# bldc_driver_board_easyeda_2.net
KiCad netlist of a schematic drawn in EasyEDA Pro
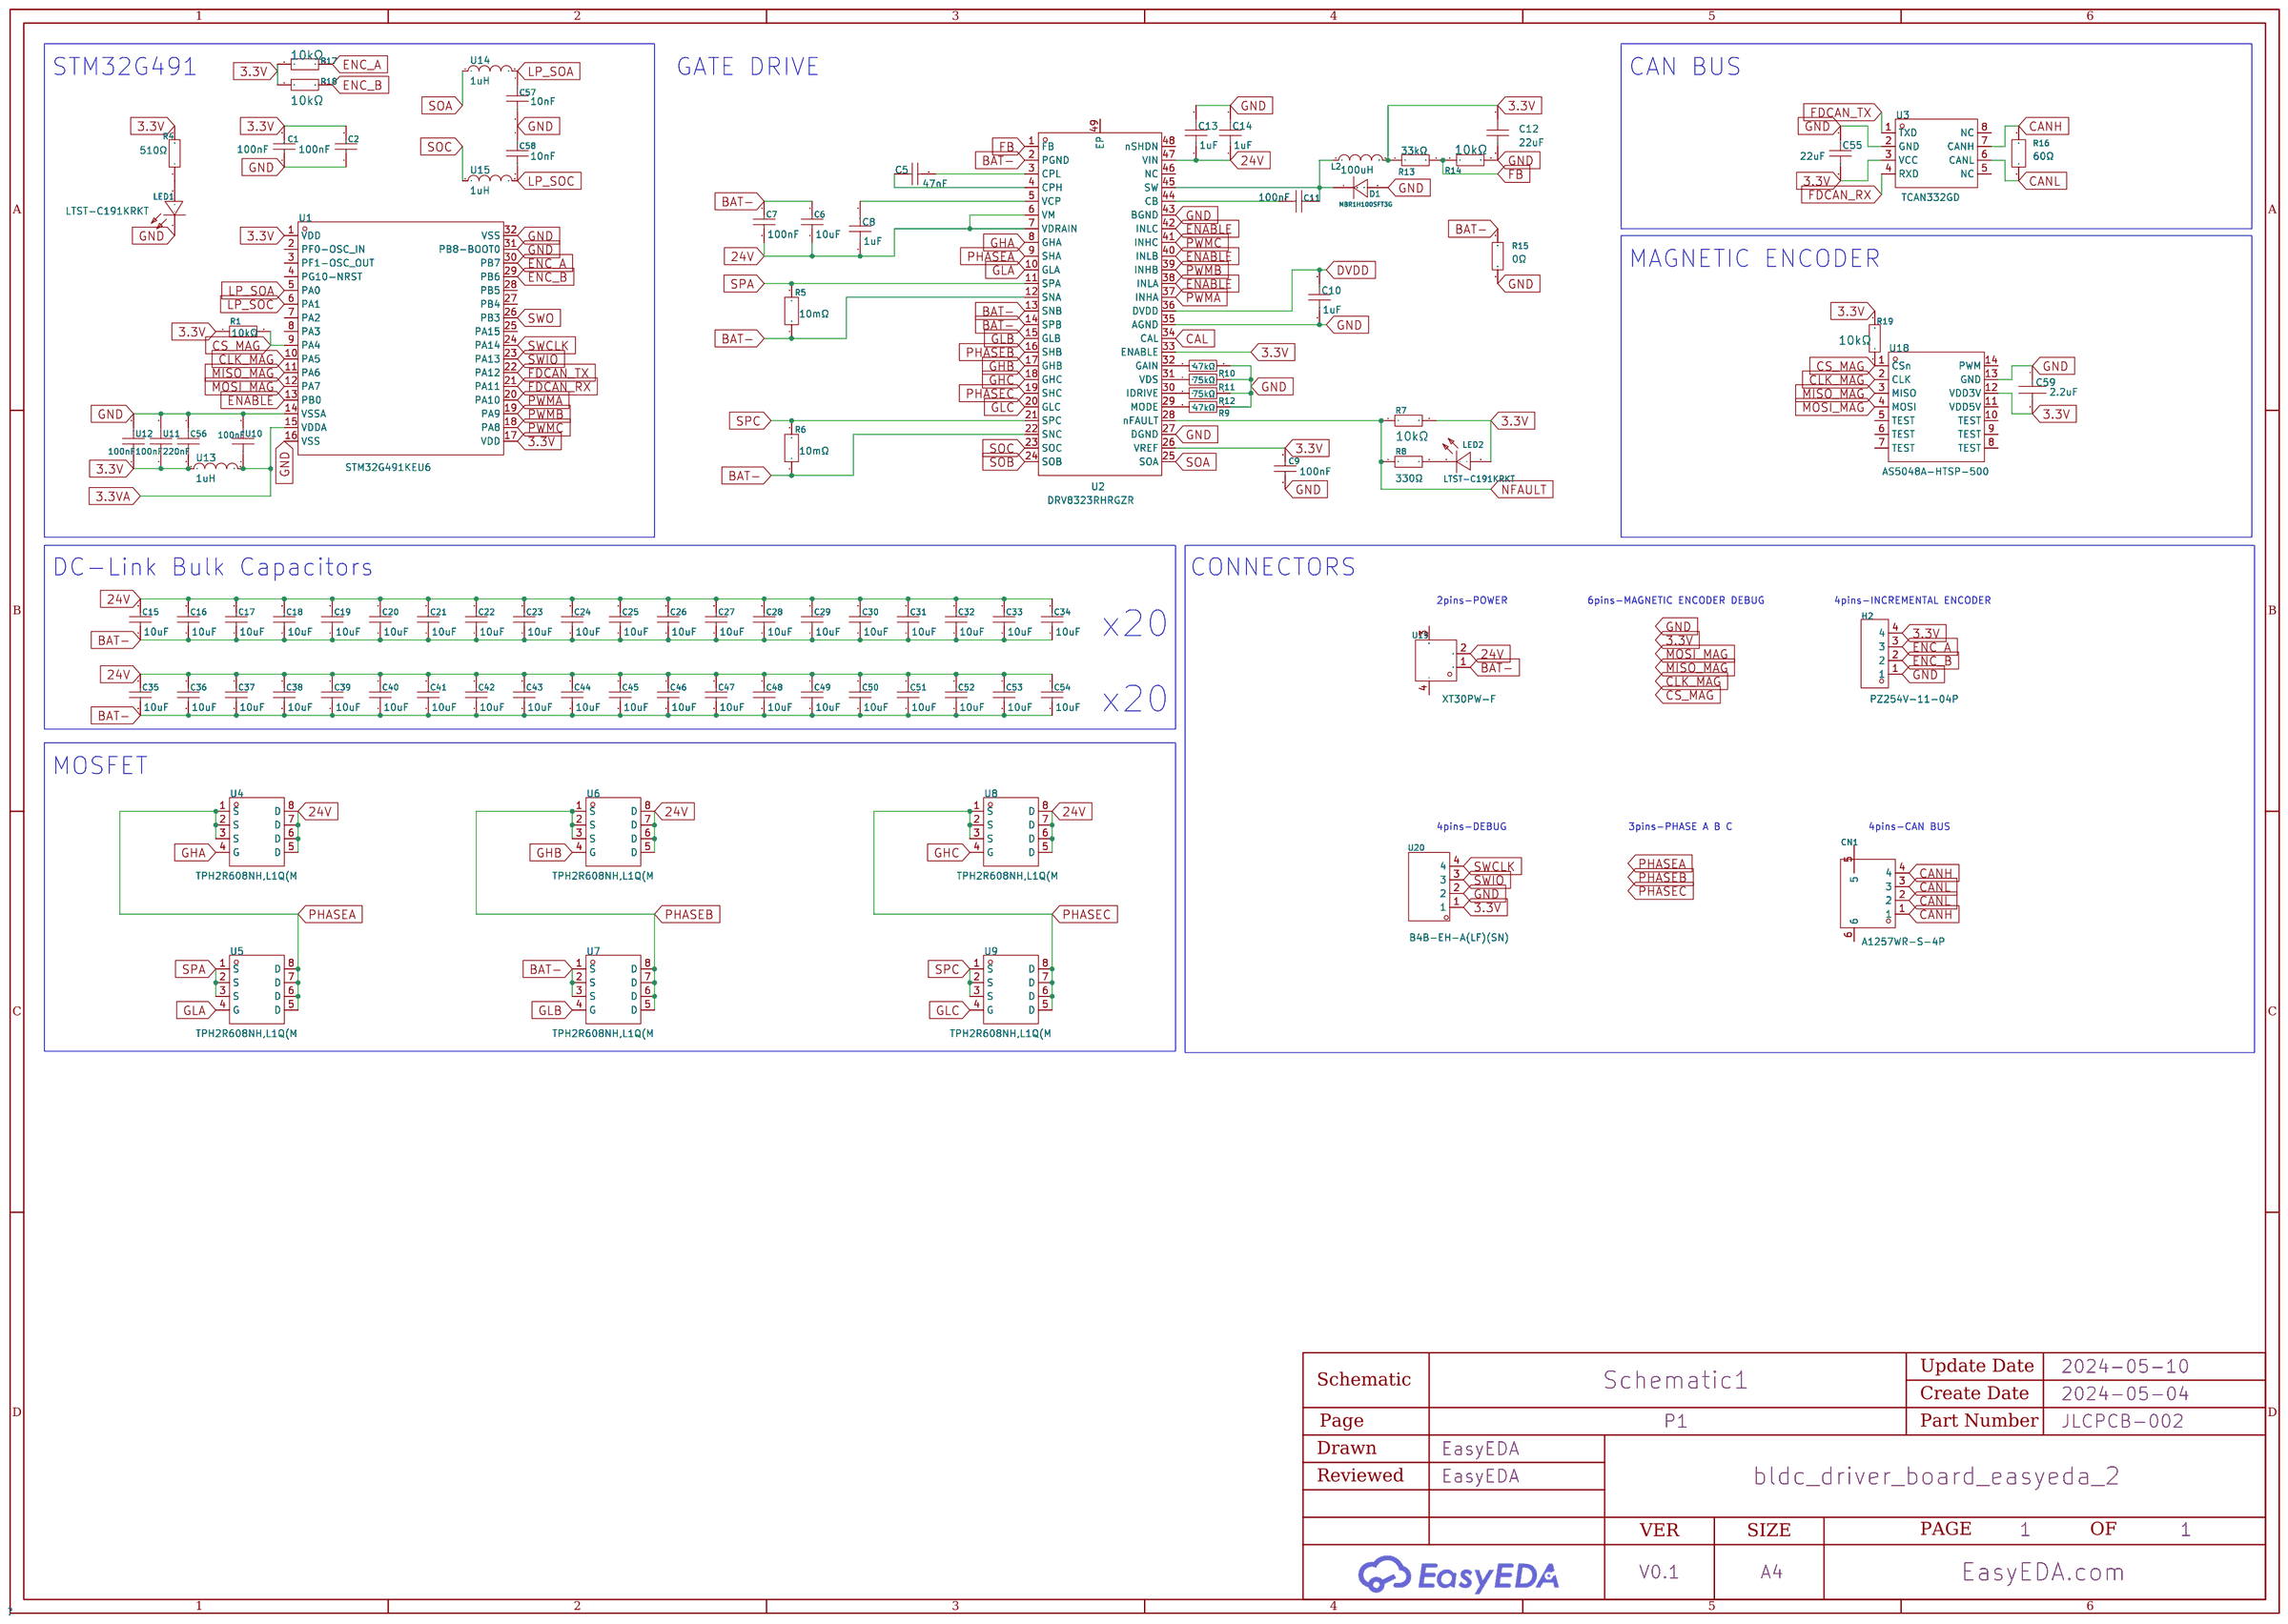
[diagram p0: schematic sheet]

(export (version "E")
  (design (tool "Eeschema 10.0.6"))
  (components
    (comp (ref "C1")
      (value "100nF")
      (footprint "easyedapro:C0603")
      (fields
        (field (name "Manufacturer Part") "CL10B104KO8NNNC")
        (field (name "Manufacturer") "SAMSUNG(三星)")
      )
      (libsource (lib "easyedapro") (part "CL10B104KO8NNNC"))
    )
    (comp (ref "C2")
      (value "100nF")
      (footprint "easyedapro:C0603")
      (fields
        (field (name "Manufacturer Part") "CL10B104KO8NNNC")
        (field (name "Manufacturer") "SAMSUNG(三星)")
      )
      (libsource (lib "easyedapro") (part "CL10B104KO8NNNC"))
    )
    (comp (ref "C5")
      (value "47nF")
      (footprint "easyedapro:C0805")
      (fields (field (name "Manufacturer Part") "0805B473K500NT") (field (name "Manufacturer") "FH(风华)"))
      (libsource (lib "easyedapro") (part "0805B473K500NT"))
    )
    (comp (ref "C6")
      (value "10uF")
      (footprint "easyedapro:C1206")
      (fields
        (field (name "Manufacturer Part") "CL31A106KBHNNNE")
        (field (name "Manufacturer") "SAMSUNG(三星)")
      )
      (libsource (lib "easyedapro") (part "CL31A106KBHNNNE"))
    )
    (comp (ref "C7")
      (value "100nF")
      (footprint "easyedapro:C1206")
      (fields (field (name "Manufacturer Part") "1206B104K500NT") (field (name "Manufacturer") "FH(风华)"))
      (libsource (lib "easyedapro") (part "1206B104K500NT"))
    )
    (comp (ref "C8")
      (value "1uF")
      (footprint "easyedapro:C0603")
      (fields
        (field (name "Manufacturer Part") "CL10A105KB8NNNC")
        (field (name "Manufacturer") "SAMSUNG(三星)")
      )
      (libsource (lib "easyedapro") (part "CL10A105KB8NNNC"))
    )
    (comp (ref "C9")
      (value "100nF")
      (footprint "easyedapro:C0603")
      (fields
        (field (name "Manufacturer Part") "CL10B104KO8NNNC")
        (field (name "Manufacturer") "SAMSUNG(三星)")
      )
      (libsource (lib "easyedapro") (part "CL10B104KO8NNNC"))
    )
    (comp (ref "C10")
      (value "1uF")
      (footprint "easyedapro:C0603")
      (fields
        (field (name "Manufacturer Part") "CL10A105KB8NNNC")
        (field (name "Manufacturer") "SAMSUNG(三星)")
      )
      (libsource (lib "easyedapro") (part "CL10A105KB8NNNC"))
    )
    (comp (ref "C11")
      (value "100nF")
      (footprint "easyedapro:C1206")
      (fields (field (name "Manufacturer Part") "1206B104K500NT") (field (name "Manufacturer") "FH(风华)"))
      (libsource (lib "easyedapro") (part "1206B104K500NT"))
    )
    (comp (ref "C12")
      (value "22uF")
      (footprint "easyedapro:C0603")
      (fields
        (field (name "Manufacturer Part") "CL10A226MQ8NRNE")
        (field (name "Manufacturer") "SAMSUNG(三星)")
      )
      (libsource (lib "easyedapro") (part "CL10A226MQ8NRNE"))
    )
    (comp (ref "C13")
      (value "1uF")
      (footprint "easyedapro:C0603")
      (fields
        (field (name "Manufacturer Part") "CL10A105KB8NNNC")
        (field (name "Manufacturer") "SAMSUNG(三星)")
      )
      (libsource (lib "easyedapro") (part "CL10A105KB8NNNC"))
    )
    (comp (ref "C14")
      (value "1uF")
      (footprint "easyedapro:C0603")
      (fields
        (field (name "Manufacturer Part") "CL10A105KB8NNNC")
        (field (name "Manufacturer") "SAMSUNG(三星)")
      )
      (libsource (lib "easyedapro") (part "CL10A105KB8NNNC"))
    )
    (comp (ref "C15")
      (value "10uF")
      (footprint "easyedapro:C1206")
      (fields
        (field (name "Manufacturer Part") "CL31A106KBHNNNE")
        (field (name "Manufacturer") "SAMSUNG(三星)")
      )
      (libsource (lib "easyedapro") (part "CL31A106KBHNNNE"))
    )
    (comp (ref "C16")
      (value "10uF")
      (footprint "easyedapro:C1206")
      (fields
        (field (name "Manufacturer Part") "CL31A106KBHNNNE")
        (field (name "Manufacturer") "SAMSUNG(三星)")
      )
      (libsource (lib "easyedapro") (part "CL31A106KBHNNNE"))
    )
    (comp (ref "C17")
      (value "10uF")
      (footprint "easyedapro:C1206")
      (fields
        (field (name "Manufacturer Part") "CL31A106KBHNNNE")
        (field (name "Manufacturer") "SAMSUNG(三星)")
      )
      (libsource (lib "easyedapro") (part "CL31A106KBHNNNE"))
    )
    (comp (ref "C18")
      (value "10uF")
      (footprint "easyedapro:C1206")
      (fields
        (field (name "Manufacturer Part") "CL31A106KBHNNNE")
        (field (name "Manufacturer") "SAMSUNG(三星)")
      )
      (libsource (lib "easyedapro") (part "CL31A106KBHNNNE"))
    )
    (comp (ref "C19")
      (value "10uF")
      (footprint "easyedapro:C1206")
      (fields
        (field (name "Manufacturer Part") "CL31A106KBHNNNE")
        (field (name "Manufacturer") "SAMSUNG(三星)")
      )
      (libsource (lib "easyedapro") (part "CL31A106KBHNNNE"))
    )
    (comp (ref "C20")
      (value "10uF")
      (footprint "easyedapro:C1206")
      (fields
        (field (name "Manufacturer Part") "CL31A106KBHNNNE")
        (field (name "Manufacturer") "SAMSUNG(三星)")
      )
      (libsource (lib "easyedapro") (part "CL31A106KBHNNNE"))
    )
    (comp (ref "C21")
      (value "10uF")
      (footprint "easyedapro:C1206")
      (fields
        (field (name "Manufacturer Part") "CL31A106KBHNNNE")
        (field (name "Manufacturer") "SAMSUNG(三星)")
      )
      (libsource (lib "easyedapro") (part "CL31A106KBHNNNE"))
    )
    (comp (ref "C22")
      (value "10uF")
      (footprint "easyedapro:C1206")
      (fields
        (field (name "Manufacturer Part") "CL31A106KBHNNNE")
        (field (name "Manufacturer") "SAMSUNG(三星)")
      )
      (libsource (lib "easyedapro") (part "CL31A106KBHNNNE"))
    )
    (comp (ref "C23")
      (value "10uF")
      (footprint "easyedapro:C1206")
      (fields
        (field (name "Manufacturer Part") "CL31A106KBHNNNE")
        (field (name "Manufacturer") "SAMSUNG(三星)")
      )
      (libsource (lib "easyedapro") (part "CL31A106KBHNNNE"))
    )
    (comp (ref "C24")
      (value "10uF")
      (footprint "easyedapro:C1206")
      (fields
        (field (name "Manufacturer Part") "CL31A106KBHNNNE")
        (field (name "Manufacturer") "SAMSUNG(三星)")
      )
      (libsource (lib "easyedapro") (part "CL31A106KBHNNNE"))
    )
    (comp (ref "C25")
      (value "10uF")
      (footprint "easyedapro:C1206")
      (fields
        (field (name "Manufacturer Part") "CL31A106KBHNNNE")
        (field (name "Manufacturer") "SAMSUNG(三星)")
      )
      (libsource (lib "easyedapro") (part "CL31A106KBHNNNE"))
    )
    (comp (ref "C26")
      (value "10uF")
      (footprint "easyedapro:C1206")
      (fields
        (field (name "Manufacturer Part") "CL31A106KBHNNNE")
        (field (name "Manufacturer") "SAMSUNG(三星)")
      )
      (libsource (lib "easyedapro") (part "CL31A106KBHNNNE"))
    )
    (comp (ref "C27")
      (value "10uF")
      (footprint "easyedapro:C1206")
      (fields
        (field (name "Manufacturer Part") "CL31A106KBHNNNE")
        (field (name "Manufacturer") "SAMSUNG(三星)")
      )
      (libsource (lib "easyedapro") (part "CL31A106KBHNNNE"))
    )
    (comp (ref "C28")
      (value "10uF")
      (footprint "easyedapro:C1206")
      (fields
        (field (name "Manufacturer Part") "CL31A106KBHNNNE")
        (field (name "Manufacturer") "SAMSUNG(三星)")
      )
      (libsource (lib "easyedapro") (part "CL31A106KBHNNNE"))
    )
    (comp (ref "C29")
      (value "10uF")
      (footprint "easyedapro:C1206")
      (fields
        (field (name "Manufacturer Part") "CL31A106KBHNNNE")
        (field (name "Manufacturer") "SAMSUNG(三星)")
      )
      (libsource (lib "easyedapro") (part "CL31A106KBHNNNE"))
    )
    (comp (ref "C30")
      (value "10uF")
      (footprint "easyedapro:C1206")
      (fields
        (field (name "Manufacturer Part") "CL31A106KBHNNNE")
        (field (name "Manufacturer") "SAMSUNG(三星)")
      )
      (libsource (lib "easyedapro") (part "CL31A106KBHNNNE"))
    )
    (comp (ref "C31")
      (value "10uF")
      (footprint "easyedapro:C1206")
      (fields
        (field (name "Manufacturer Part") "CL31A106KBHNNNE")
        (field (name "Manufacturer") "SAMSUNG(三星)")
      )
      (libsource (lib "easyedapro") (part "CL31A106KBHNNNE"))
    )
    (comp (ref "C32")
      (value "10uF")
      (footprint "easyedapro:C1206")
      (fields
        (field (name "Manufacturer Part") "CL31A106KBHNNNE")
        (field (name "Manufacturer") "SAMSUNG(三星)")
      )
      (libsource (lib "easyedapro") (part "CL31A106KBHNNNE"))
    )
    (comp (ref "C33")
      (value "10uF")
      (footprint "easyedapro:C1206")
      (fields
        (field (name "Manufacturer Part") "CL31A106KBHNNNE")
        (field (name "Manufacturer") "SAMSUNG(三星)")
      )
      (libsource (lib "easyedapro") (part "CL31A106KBHNNNE"))
    )
    (comp (ref "C34")
      (value "10uF")
      (footprint "easyedapro:C1206")
      (fields
        (field (name "Manufacturer Part") "CL31A106KBHNNNE")
        (field (name "Manufacturer") "SAMSUNG(三星)")
      )
      (libsource (lib "easyedapro") (part "CL31A106KBHNNNE"))
    )
    (comp (ref "C35")
      (value "10uF")
      (footprint "easyedapro:C1206")
      (fields
        (field (name "Manufacturer Part") "CL31A106KBHNNNE")
        (field (name "Manufacturer") "SAMSUNG(三星)")
      )
      (libsource (lib "easyedapro") (part "CL31A106KBHNNNE"))
    )
    (comp (ref "C36")
      (value "10uF")
      (footprint "easyedapro:C1206")
      (fields
        (field (name "Manufacturer Part") "CL31A106KBHNNNE")
        (field (name "Manufacturer") "SAMSUNG(三星)")
      )
      (libsource (lib "easyedapro") (part "CL31A106KBHNNNE"))
    )
    (comp (ref "C37")
      (value "10uF")
      (footprint "easyedapro:C1206")
      (fields
        (field (name "Manufacturer Part") "CL31A106KBHNNNE")
        (field (name "Manufacturer") "SAMSUNG(三星)")
      )
      (libsource (lib "easyedapro") (part "CL31A106KBHNNNE"))
    )
    (comp (ref "C38")
      (value "10uF")
      (footprint "easyedapro:C1206")
      (fields
        (field (name "Manufacturer Part") "CL31A106KBHNNNE")
        (field (name "Manufacturer") "SAMSUNG(三星)")
      )
      (libsource (lib "easyedapro") (part "CL31A106KBHNNNE"))
    )
    (comp (ref "C39")
      (value "10uF")
      (footprint "easyedapro:C1206")
      (fields
        (field (name "Manufacturer Part") "CL31A106KBHNNNE")
        (field (name "Manufacturer") "SAMSUNG(三星)")
      )
      (libsource (lib "easyedapro") (part "CL31A106KBHNNNE"))
    )
    (comp (ref "C40")
      (value "10uF")
      (footprint "easyedapro:C1206")
      (fields
        (field (name "Manufacturer Part") "CL31A106KBHNNNE")
        (field (name "Manufacturer") "SAMSUNG(三星)")
      )
      (libsource (lib "easyedapro") (part "CL31A106KBHNNNE"))
    )
    (comp (ref "C41")
      (value "10uF")
      (footprint "easyedapro:C1206")
      (fields
        (field (name "Manufacturer Part") "CL31A106KBHNNNE")
        (field (name "Manufacturer") "SAMSUNG(三星)")
      )
      (libsource (lib "easyedapro") (part "CL31A106KBHNNNE"))
    )
    (comp (ref "C42")
      (value "10uF")
      (footprint "easyedapro:C1206")
      (fields
        (field (name "Manufacturer Part") "CL31A106KBHNNNE")
        (field (name "Manufacturer") "SAMSUNG(三星)")
      )
      (libsource (lib "easyedapro") (part "CL31A106KBHNNNE"))
    )
    (comp (ref "C43")
      (value "10uF")
      (footprint "easyedapro:C1206")
      (fields
        (field (name "Manufacturer Part") "CL31A106KBHNNNE")
        (field (name "Manufacturer") "SAMSUNG(三星)")
      )
      (libsource (lib "easyedapro") (part "CL31A106KBHNNNE"))
    )
    (comp (ref "C44")
      (value "10uF")
      (footprint "easyedapro:C1206")
      (fields
        (field (name "Manufacturer Part") "CL31A106KBHNNNE")
        (field (name "Manufacturer") "SAMSUNG(三星)")
      )
      (libsource (lib "easyedapro") (part "CL31A106KBHNNNE"))
    )
    (comp (ref "C45")
      (value "10uF")
      (footprint "easyedapro:C1206")
      (fields
        (field (name "Manufacturer Part") "CL31A106KBHNNNE")
        (field (name "Manufacturer") "SAMSUNG(三星)")
      )
      (libsource (lib "easyedapro") (part "CL31A106KBHNNNE"))
    )
    (comp (ref "C46")
      (value "10uF")
      (footprint "easyedapro:C1206")
      (fields
        (field (name "Manufacturer Part") "CL31A106KBHNNNE")
        (field (name "Manufacturer") "SAMSUNG(三星)")
      )
      (libsource (lib "easyedapro") (part "CL31A106KBHNNNE"))
    )
    (comp (ref "C47")
      (value "10uF")
      (footprint "easyedapro:C1206")
      (fields
        (field (name "Manufacturer Part") "CL31A106KBHNNNE")
        (field (name "Manufacturer") "SAMSUNG(三星)")
      )
      (libsource (lib "easyedapro") (part "CL31A106KBHNNNE"))
    )
    (comp (ref "C48")
      (value "10uF")
      (footprint "easyedapro:C1206")
      (fields
        (field (name "Manufacturer Part") "CL31A106KBHNNNE")
        (field (name "Manufacturer") "SAMSUNG(三星)")
      )
      (libsource (lib "easyedapro") (part "CL31A106KBHNNNE"))
    )
    (comp (ref "C49")
      (value "10uF")
      (footprint "easyedapro:C1206")
      (fields
        (field (name "Manufacturer Part") "CL31A106KBHNNNE")
        (field (name "Manufacturer") "SAMSUNG(三星)")
      )
      (libsource (lib "easyedapro") (part "CL31A106KBHNNNE"))
    )
    (comp (ref "C50")
      (value "10uF")
      (footprint "easyedapro:C1206")
      (fields
        (field (name "Manufacturer Part") "CL31A106KBHNNNE")
        (field (name "Manufacturer") "SAMSUNG(三星)")
      )
      (libsource (lib "easyedapro") (part "CL31A106KBHNNNE"))
    )
    (comp (ref "C51")
      (value "10uF")
      (footprint "easyedapro:C1206")
      (fields
        (field (name "Manufacturer Part") "CL31A106KBHNNNE")
        (field (name "Manufacturer") "SAMSUNG(三星)")
      )
      (libsource (lib "easyedapro") (part "CL31A106KBHNNNE"))
    )
    (comp (ref "C52")
      (value "10uF")
      (footprint "easyedapro:C1206")
      (fields
        (field (name "Manufacturer Part") "CL31A106KBHNNNE")
        (field (name "Manufacturer") "SAMSUNG(三星)")
      )
      (libsource (lib "easyedapro") (part "CL31A106KBHNNNE"))
    )
    (comp (ref "C53")
      (value "10uF")
      (footprint "easyedapro:C1206")
      (fields
        (field (name "Manufacturer Part") "CL31A106KBHNNNE")
        (field (name "Manufacturer") "SAMSUNG(三星)")
      )
      (libsource (lib "easyedapro") (part "CL31A106KBHNNNE"))
    )
    (comp (ref "C54")
      (value "10uF")
      (footprint "easyedapro:C1206")
      (fields
        (field (name "Manufacturer Part") "CL31A106KBHNNNE")
        (field (name "Manufacturer") "SAMSUNG(三星)")
      )
      (libsource (lib "easyedapro") (part "CL31A106KBHNNNE"))
    )
    (comp (ref "C55")
      (value "22uF")
      (footprint "easyedapro:C0603")
      (fields
        (field (name "Manufacturer Part") "CL10A226MQ8NRNE")
        (field (name "Manufacturer") "SAMSUNG(三星)")
      )
      (libsource (lib "easyedapro") (part "CL10A226MQ8NRNE"))
    )
    (comp (ref "C56")
      (value "220nF")
      (footprint "easyedapro:C0201")
      (fields (field (name "Manufacturer Part") "C0603X5R0J224KT00NN") (field (name "Manufacturer") "TDK"))
      (libsource (lib "easyedapro") (part "C0603X5R0J224KT00NN"))
    )
    (comp (ref "C57")
      (value "10nF")
      (footprint "easyedapro:C01005")
      (fields
        (field (name "Manufacturer Part") "CC0603KRX7R9BB103")
        (field (name "Manufacturer") "YAGEO(国巨)")
      )
      (libsource (lib "easyedapro") (part "CC0100KRX5R5BB103"))
    )
    (comp (ref "C58")
      (value "10nF")
      (footprint "easyedapro:C01005")
      (fields
        (field (name "Manufacturer Part") "CC0603KRX7R9BB103")
        (field (name "Manufacturer") "YAGEO(国巨)")
      )
      (libsource (lib "easyedapro") (part "CC0100KRX5R5BB103"))
    )
    (comp (ref "C59")
      (value "2.2uF")
      (footprint "easyedapro:C0402")
      (fields
        (field (name "Manufacturer Part") "CL05A225MQ5NSNC")
        (field (name "Manufacturer") "SAMSUNG(三星)")
      )
      (libsource (lib "easyedapro") (part "CL05A225MQ5NSNC"))
    )
    (comp (ref "CN1")
      (value "A1257WR-S-4P")
      (footprint "easyedapro:CONN-SMD_A1257WR-S-4P")
      (fields (field (name "Manufacturer") "CJT(长江连接器)"))
      (libsource (lib "easyedapro") (part "A1257WR-S-4P"))
    )
    (comp (ref "D1")
      (value "MBR1H100SFT3G")
      (footprint "easyedapro:SOD-123F_L2.8-W1.8-LS3.7-RD")
      (fields (field (name "Manufacturer") "onsemi(安森美)"))
      (libsource (lib "easyedapro") (part "MBR1H100SFT3G"))
    )
    (comp (ref "H2")
      (value "PZ254V-11-04P")
      (footprint "easyedapro:HDR-TH_4P-P2.54-V-M")
      (fields (field (name "Manufacturer") "XFCN(兴飞)"))
      (libsource (lib "easyedapro") (part "PZ254V-11-04P"))
    )
    (comp (ref "L2")
      (value "100uH")
      (footprint "easyedapro:IND-SMD_L4.0-W4.0")
      (fields
        (field (name "Manufacturer Part") "ASPIAIG-S4035-101M-T")
        (field (name "Manufacturer") "ABRACON")
      )
      (libsource (lib "easyedapro") (part "ASPIAIG-S4035-101M-T"))
    )
    (comp (ref "LED1")
      (value "LTST-C191KRKT")
      (footprint "easyedapro:LED0603-RD")
      (fields (field (name "Manufacturer") "LITEON(光宝)"))
      (libsource (lib "easyedapro") (part "LTST-C191KRKT"))
    )
    (comp (ref "LED2")
      (value "LTST-C191KRKT")
      (footprint "easyedapro:LED0603-RD")
      (fields (field (name "Manufacturer") "LITEON(光宝)"))
      (libsource (lib "easyedapro") (part "LTST-C191KRKT"))
    )
    (comp (ref "R1")
      (value "10kΩ")
      (footprint "easyedapro:R0603")
      (fields
        (field (name "Manufacturer Part") "0603WAF1002T5E")
        (field (name "Manufacturer") "UNI-ROYAL(厚声)")
      )
      (libsource (lib "easyedapro") (part "0603WAF1002T5E"))
    )
    (comp (ref "R4")
      (value "510Ω")
      (footprint "easyedapro:R0603")
      (fields
        (field (name "Manufacturer Part") "0603WAF5100T5E")
        (field (name "Manufacturer") "UNI-ROYAL(厚声)")
      )
      (libsource (lib "easyedapro") (part "0603WAF5100T5E"))
    )
    (comp (ref "R5")
      (value "10mΩ")
      (footprint "easyedapro:RES-SMD_L6.4-W3.2-R2512")
      (fields
        (field (name "Manufacturer Part") "HoJLR2512-3W-10mR-1%")
        (field (name "Manufacturer") "Milliohm(毫欧)")
      )
      (libsource (lib "easyedapro") (part "HOJLR2512-3W-10MR-1%"))
    )
    (comp (ref "R6")
      (value "10mΩ")
      (footprint "easyedapro:RES-SMD_L6.4-W3.2-R2512")
      (fields
        (field (name "Manufacturer Part") "HoJLR2512-3W-10mR-1%")
        (field (name "Manufacturer") "Milliohm(毫欧)")
      )
      (libsource (lib "easyedapro") (part "HOJLR2512-3W-10MR-1%"))
    )
    (comp (ref "R7")
      (value "10kΩ")
      (footprint "easyedapro:R0603")
      (fields
        (field (name "Manufacturer Part") "0603WAF1002T5E")
        (field (name "Manufacturer") "UNI-ROYAL(厚声)")
      )
      (libsource (lib "easyedapro") (part "0603WAF1002T5E"))
    )
    (comp (ref "R8")
      (value "330Ω")
      (footprint "easyedapro:R0603")
      (fields
        (field (name "Manufacturer Part") "0603WAF3300T5E")
        (field (name "Manufacturer") "UNI-ROYAL(厚声)")
      )
      (libsource (lib "easyedapro") (part "0603WAF3300T5E"))
    )
    (comp (ref "R9")
      (value "47kΩ")
      (footprint "easyedapro:R0603")
      (fields
        (field (name "Manufacturer Part") "0603WAF4702T5E")
        (field (name "Manufacturer") "UNI-ROYAL(厚声)")
      )
      (libsource (lib "easyedapro") (part "0603WAF4702T5E"))
    )
    (comp (ref "R10")
      (value "47kΩ")
      (footprint "easyedapro:R0603")
      (fields
        (field (name "Manufacturer Part") "0603WAF4702T5E")
        (field (name "Manufacturer") "UNI-ROYAL(厚声)")
      )
      (libsource (lib "easyedapro") (part "0603WAF4702T5E"))
    )
    (comp (ref "R11")
      (value "75kΩ")
      (footprint "easyedapro:R0603")
      (fields
        (field (name "Manufacturer Part") "0603WAF7502T5E")
        (field (name "Manufacturer") "UNI-ROYAL(厚声)")
      )
      (libsource (lib "easyedapro") (part "0603WAF7502T5E"))
    )
    (comp (ref "R12")
      (value "75kΩ")
      (footprint "easyedapro:R0603")
      (fields
        (field (name "Manufacturer Part") "0603WAF7502T5E")
        (field (name "Manufacturer") "UNI-ROYAL(厚声)")
      )
      (libsource (lib "easyedapro") (part "0603WAF7502T5E"))
    )
    (comp (ref "R13")
      (value "33kΩ")
      (footprint "easyedapro:R0603")
      (fields
        (field (name "Manufacturer Part") "0603WAF3302T5E")
        (field (name "Manufacturer") "UNI-ROYAL(厚声)")
      )
      (libsource (lib "easyedapro") (part "0603WAF3302T5E"))
    )
    (comp (ref "R14")
      (value "10kΩ")
      (footprint "easyedapro:R0603")
      (fields
        (field (name "Manufacturer Part") "0603WAF1002T5E")
        (field (name "Manufacturer") "UNI-ROYAL(厚声)")
      )
      (libsource (lib "easyedapro") (part "0603WAF1002T5E"))
    )
    (comp (ref "R15")
      (value "0Ω")
      (footprint "easyedapro:R1206")
      (fields
        (field (name "Manufacturer Part") "1206W4F0000T5E")
        (field (name "Manufacturer") "UNI-ROYAL(厚声)")
      )
      (libsource (lib "easyedapro") (part "1206W4F0000T5E"))
    )
    (comp (ref "R16")
      (value "60Ω")
      (footprint "easyedapro:R0603")
      (fields (field (name "Manufacturer Part") "RTT0360R0FTP") (field (name "Manufacturer") "RALEC(旺诠)"))
      (libsource (lib "easyedapro") (part "RTT0360R0FTP"))
    )
    (comp (ref "R17")
      (value "10kΩ")
      (footprint "easyedapro:R0603")
      (fields
        (field (name "Manufacturer Part") "0603WAF1002T5E")
        (field (name "Manufacturer") "UNI-ROYAL(厚声)")
      )
      (libsource (lib "easyedapro") (part "0603WAF1002T5E"))
    )
    (comp (ref "R18")
      (value "10kΩ")
      (footprint "easyedapro:R0603")
      (fields
        (field (name "Manufacturer Part") "0603WAF1002T5E")
        (field (name "Manufacturer") "UNI-ROYAL(厚声)")
      )
      (libsource (lib "easyedapro") (part "0603WAF1002T5E"))
    )
    (comp (ref "R19")
      (value "10kΩ")
      (footprint "easyedapro:R0603")
      (fields
        (field (name "Manufacturer Part") "0603WAF1002T5E")
        (field (name "Manufacturer") "UNI-ROYAL(厚声)")
      )
      (libsource (lib "easyedapro") (part "0603WAF1002T5E"))
    )
    (comp (ref "U1")
      (value "STM32G491KEU6")
      (footprint "easyedapro:UFQFPN-32_L5.0-W5.0-P0.50-TL-1")
      (fields (field (name "Manufacturer") "ST(意法半导体)"))
      (libsource (lib "easyedapro") (part "STM32G491KEU6"))
    )
    (comp (ref "U2")
      (value "DRV8323RHRGZR")
      (footprint "easyedapro:VQFN-48_L7.0-W7.0-P0.50-TL-EP5.1")
      (fields (field (name "Manufacturer") "TI(德州仪器)"))
      (libsource (lib "easyedapro") (part "DRV8323RHRGZR"))
    )
    (comp (ref "U3")
      (value "TCAN332GD")
      (footprint "easyedapro:SOIC-8_L4.9-W3.9-P1.27-LS6.0-BL")
      (fields (field (name "Manufacturer") "TI(德州仪器)"))
      (libsource (lib "easyedapro") (part "TCAN332GD"))
    )
    (comp (ref "U4")
      (value "TPH2R608NH,L1Q(M")
      (footprint "easyedapro:POWERVDFN-8_L5.0-W5.0-P1.27-LS6.0-BL")
      (fields (field (name "Manufacturer") "TOSHIBA(东芝)"))
      (libsource (lib "easyedapro") (part "TPH2R608NH,L1Q(M"))
    )
    (comp (ref "U5")
      (value "TPH2R608NH,L1Q(M")
      (footprint "easyedapro:POWERVDFN-8_L5.0-W5.0-P1.27-LS6.0-BL")
      (fields (field (name "Manufacturer") "TOSHIBA(东芝)"))
      (libsource (lib "easyedapro") (part "TPH2R608NH,L1Q(M"))
    )
    (comp (ref "U6")
      (value "TPH2R608NH,L1Q(M")
      (footprint "easyedapro:POWERVDFN-8_L5.0-W5.0-P1.27-LS6.0-BL")
      (fields (field (name "Manufacturer") "TOSHIBA(东芝)"))
      (libsource (lib "easyedapro") (part "TPH2R608NH,L1Q(M"))
    )
    (comp (ref "U7")
      (value "TPH2R608NH,L1Q(M")
      (footprint "easyedapro:POWERVDFN-8_L5.0-W5.0-P1.27-LS6.0-BL")
      (fields (field (name "Manufacturer") "TOSHIBA(东芝)"))
      (libsource (lib "easyedapro") (part "TPH2R608NH,L1Q(M"))
    )
    (comp (ref "U8")
      (value "TPH2R608NH,L1Q(M")
      (footprint "easyedapro:POWERVDFN-8_L5.0-W5.0-P1.27-LS6.0-BL")
      (fields (field (name "Manufacturer") "TOSHIBA(东芝)"))
      (libsource (lib "easyedapro") (part "TPH2R608NH,L1Q(M"))
    )
    (comp (ref "U9")
      (value "TPH2R608NH,L1Q(M")
      (footprint "easyedapro:POWERVDFN-8_L5.0-W5.0-P1.27-LS6.0-BL")
      (fields (field (name "Manufacturer") "TOSHIBA(东芝)"))
      (libsource (lib "easyedapro") (part "TPH2R608NH,L1Q(M"))
    )
    (comp (ref "U10")
      (value "100nF")
      (footprint "easyedapro:C0603")
      (fields (field (name "Manufacturer Part") "06036D104KAT2A") (field (name "Manufacturer") "Kyocera AVX"))
      (libsource (lib "easyedapro") (part "06036D104KAT2A"))
    )
    (comp (ref "U11")
      (value "100nF")
      (footprint "easyedapro:C0603")
      (fields (field (name "Manufacturer Part") "06036D104KAT2A") (field (name "Manufacturer") "Kyocera AVX"))
      (libsource (lib "easyedapro") (part "06036D104KAT2A"))
    )
    (comp (ref "U12")
      (value "100nF")
      (footprint "easyedapro:C0603")
      (fields (field (name "Manufacturer Part") "06036D104KAT2A") (field (name "Manufacturer") "Kyocera AVX"))
      (libsource (lib "easyedapro") (part "06036D104KAT2A"))
    )
    (comp (ref "U13")
      (value "1uH")
      (footprint "easyedapro:L0603")
      (fields (field (name "Manufacturer Part") "YL160808-1R0K") (field (name "Manufacturer") "YJYCOIN(益嘉源)"))
      (libsource (lib "easyedapro") (part "YL160808-1R0K"))
    )
    (comp (ref "U14")
      (value "1uH")
      (footprint "easyedapro:L0603")
      (fields (field (name "Manufacturer Part") "YL160808-1R0K") (field (name "Manufacturer") "YJYCOIN(益嘉源)"))
      (libsource (lib "easyedapro") (part "YL160808-1R0K"))
    )
    (comp (ref "U15")
      (value "1uH")
      (footprint "easyedapro:L0603")
      (fields (field (name "Manufacturer Part") "YL160808-1R0K") (field (name "Manufacturer") "YJYCOIN(益嘉源)"))
      (libsource (lib "easyedapro") (part "YL160808-1R0K"))
    )
    (comp (ref "U18")
      (value "AS5048A-HTSP-500")
      (footprint "easyedapro:TSSOP-14_L5.0-W4.4-P0.65-LS6.4-BL")
      (fields (field (name "Manufacturer") "ams(艾迈斯半导体)"))
      (libsource (lib "easyedapro") (part "AS5048A-HTSP-500"))
    )
    (comp (ref "U19")
      (value "XT30PW-F")
      (footprint "easyedapro:CONN-TH_XT30PW-F-1")
      (fields (field (name "Manufacturer") "AMASS(艾迈斯)"))
      (libsource (lib "easyedapro") (part "XT30PW-F"))
    )
    (comp (ref "U20")
      (value "B4B-EH-A(LF)(SN)")
      (footprint "easyedapro:CONN-TH_B4B-EH-A-LF-SN")
      (fields (field (name "Manufacturer") "JST"))
      (libsource (lib "easyedapro") (part "B4B-EH-A(LF)(SN)"))
    )
  )
  (nets
    (net (code "1") (name "3.3V") (class "Default")
      (node (ref "C1") (pin "2") (pinfunction "2_2") (pintype "input"))
      (node (ref "C12") (pin "1") (pinfunction "1_1") (pintype "unspecified"))
      (node (ref "C2") (pin "2") (pinfunction "2_2") (pintype "input"))
      (node (ref "C55") (pin "2") (pinfunction "2_2") (pintype "unspecified"))
      (node (ref "C56") (pin "2") (pinfunction "2_2") (pintype "input"))
      (node (ref "C59") (pin "2") (pinfunction "2_2") (pintype "unspecified"))
      (node (ref "C9") (pin "2") (pinfunction "2_2") (pintype "input"))
      (node (ref "H2") (pin "4") (pinfunction "4_4") (pintype "unspecified"))
      (node (ref "L2") (pin "2") (pinfunction "2_2") (pintype "input"))
      (node (ref "LED2") (pin "2") (pinfunction "+_2") (pintype "input"))
      (node (ref "R1") (pin "1") (pinfunction "1_1") (pintype "input"))
      (node (ref "R13") (pin "1") (pinfunction "1_1") (pintype "input"))
      (node (ref "R17") (pin "1") (pinfunction "1_1") (pintype "input"))
      (node (ref "R18") (pin "1") (pinfunction "1_1") (pintype "input"))
      (node (ref "R19") (pin "2") (pinfunction "2_2") (pintype "input"))
      (node (ref "R4") (pin "2") (pinfunction "2_2") (pintype "input"))
      (node (ref "R7") (pin "2") (pinfunction "2_2") (pintype "input"))
      (node (ref "U1") (pin "1") (pinfunction "VDD_1") (pintype "unspecified"))
      (node (ref "U1") (pin "17") (pinfunction "VDD_17") (pintype "unspecified"))
      (node (ref "U11") (pin "1") (pinfunction "1_1") (pintype "unspecified"))
      (node (ref "U12") (pin "1") (pinfunction "1_1") (pintype "unspecified"))
      (node (ref "U13") (pin "1") (pinfunction "1_1") (pintype "unspecified"))
      (node (ref "U18") (pin "12") (pinfunction "VDD3V_12") (pintype "unspecified"))
      (node (ref "U2") (pin "26") (pinfunction "VREF_26") (pintype "input"))
      (node (ref "U2") (pin "33") (pinfunction "ENABLE_33") (pintype "input"))
      (node (ref "U20") (pin "1") (pinfunction "1_1") (pintype "input"))
      (node (ref "U3") (pin "3") (pinfunction "VCC_3") (pintype "unspecified"))
    )
    (net (code "2") (name "3.3VA") (class "Default")
      (node (ref "U1") (pin "15") (pinfunction "VDDA_15") (pintype "unspecified"))
      (node (ref "U10") (pin "1") (pinfunction "1_1") (pintype "unspecified"))
      (node (ref "U13") (pin "2") (pinfunction "2_2") (pintype "unspecified"))
    )
    (net (code "3") (name "24V") (class "Default")
      (node (ref "C13") (pin "1") (pinfunction "1_1") (pintype "unspecified"))
      (node (ref "C14") (pin "1") (pinfunction "1_1") (pintype "unspecified"))
      (node (ref "C15") (pin "2") (pinfunction "2_2") (pintype "input"))
      (node (ref "C16") (pin "2") (pinfunction "2_2") (pintype "input"))
      (node (ref "C17") (pin "2") (pinfunction "2_2") (pintype "input"))
      (node (ref "C18") (pin "2") (pinfunction "2_2") (pintype "input"))
      (node (ref "C19") (pin "2") (pinfunction "2_2") (pintype "input"))
      (node (ref "C20") (pin "2") (pinfunction "2_2") (pintype "input"))
      (node (ref "C21") (pin "2") (pinfunction "2_2") (pintype "input"))
      (node (ref "C22") (pin "2") (pinfunction "2_2") (pintype "input"))
      (node (ref "C23") (pin "2") (pinfunction "2_2") (pintype "input"))
      (node (ref "C24") (pin "2") (pinfunction "2_2") (pintype "input"))
      (node (ref "C25") (pin "2") (pinfunction "2_2") (pintype "input"))
      (node (ref "C26") (pin "2") (pinfunction "2_2") (pintype "input"))
      (node (ref "C27") (pin "2") (pinfunction "2_2") (pintype "input"))
      (node (ref "C28") (pin "2") (pinfunction "2_2") (pintype "input"))
      (node (ref "C29") (pin "2") (pinfunction "2_2") (pintype "input"))
      (node (ref "C30") (pin "2") (pinfunction "2_2") (pintype "input"))
      (node (ref "C31") (pin "2") (pinfunction "2_2") (pintype "input"))
      (node (ref "C32") (pin "2") (pinfunction "2_2") (pintype "input"))
      (node (ref "C33") (pin "2") (pinfunction "2_2") (pintype "input"))
      (node (ref "C34") (pin "2") (pinfunction "2_2") (pintype "input"))
      (node (ref "C35") (pin "2") (pinfunction "2_2") (pintype "input"))
      (node (ref "C36") (pin "2") (pinfunction "2_2") (pintype "input"))
      (node (ref "C37") (pin "2") (pinfunction "2_2") (pintype "input"))
      (node (ref "C38") (pin "2") (pinfunction "2_2") (pintype "input"))
      (node (ref "C39") (pin "2") (pinfunction "2_2") (pintype "input"))
      (node (ref "C40") (pin "2") (pinfunction "2_2") (pintype "input"))
      (node (ref "C41") (pin "2") (pinfunction "2_2") (pintype "input"))
      (node (ref "C42") (pin "2") (pinfunction "2_2") (pintype "input"))
      (node (ref "C43") (pin "2") (pinfunction "2_2") (pintype "input"))
      (node (ref "C44") (pin "2") (pinfunction "2_2") (pintype "input"))
      (node (ref "C45") (pin "2") (pinfunction "2_2") (pintype "input"))
      (node (ref "C46") (pin "2") (pinfunction "2_2") (pintype "input"))
      (node (ref "C47") (pin "2") (pinfunction "2_2") (pintype "input"))
      (node (ref "C48") (pin "2") (pinfunction "2_2") (pintype "input"))
      (node (ref "C49") (pin "2") (pinfunction "2_2") (pintype "input"))
      (node (ref "C50") (pin "2") (pinfunction "2_2") (pintype "input"))
      (node (ref "C51") (pin "2") (pinfunction "2_2") (pintype "input"))
      (node (ref "C52") (pin "2") (pinfunction "2_2") (pintype "input"))
      (node (ref "C53") (pin "2") (pinfunction "2_2") (pintype "input"))
      (node (ref "C54") (pin "2") (pinfunction "2_2") (pintype "input"))
      (node (ref "C6") (pin "1") (pinfunction "1_1") (pintype "input"))
      (node (ref "C7") (pin "1") (pinfunction "1_1") (pintype "input"))
      (node (ref "C8") (pin "1") (pinfunction "1_1") (pintype "unspecified"))
      (node (ref "U19") (pin "2") (pinfunction "2_2") (pintype "unspecified"))
      (node (ref "U2") (pin "47") (pinfunction "VIN_47") (pintype "input"))
      (node (ref "U2") (pin "6") (pinfunction "VM_6") (pintype "input"))
      (node (ref "U2") (pin "7") (pinfunction "VDRAIN_7") (pintype "input"))
      (node (ref "U4") (pin "5") (pinfunction "D_5") (pintype "input"))
      (node (ref "U4") (pin "6") (pinfunction "D_6") (pintype "input"))
      (node (ref "U4") (pin "7") (pinfunction "D_7") (pintype "input"))
      (node (ref "U4") (pin "8") (pinfunction "D_8") (pintype "input"))
      (node (ref "U6") (pin "5") (pinfunction "D_5") (pintype "input"))
      (node (ref "U6") (pin "6") (pinfunction "D_6") (pintype "input"))
      (node (ref "U6") (pin "7") (pinfunction "D_7") (pintype "input"))
      (node (ref "U6") (pin "8") (pinfunction "D_8") (pintype "input"))
      (node (ref "U8") (pin "5") (pinfunction "D_5") (pintype "input"))
      (node (ref "U8") (pin "6") (pinfunction "D_6") (pintype "input"))
      (node (ref "U8") (pin "7") (pinfunction "D_7") (pintype "input"))
      (node (ref "U8") (pin "8") (pinfunction "D_8") (pintype "input"))
    )
    (net (code "4") (name "BAT-") (class "Default")
      (node (ref "C15") (pin "1") (pinfunction "1_1") (pintype "input"))
      (node (ref "C16") (pin "1") (pinfunction "1_1") (pintype "input"))
      (node (ref "C17") (pin "1") (pinfunction "1_1") (pintype "input"))
      (node (ref "C18") (pin "1") (pinfunction "1_1") (pintype "input"))
      (node (ref "C19") (pin "1") (pinfunction "1_1") (pintype "input"))
      (node (ref "C20") (pin "1") (pinfunction "1_1") (pintype "input"))
      (node (ref "C21") (pin "1") (pinfunction "1_1") (pintype "input"))
      (node (ref "C22") (pin "1") (pinfunction "1_1") (pintype "input"))
      (node (ref "C23") (pin "1") (pinfunction "1_1") (pintype "input"))
      (node (ref "C24") (pin "1") (pinfunction "1_1") (pintype "input"))
      (node (ref "C25") (pin "1") (pinfunction "1_1") (pintype "input"))
      (node (ref "C26") (pin "1") (pinfunction "1_1") (pintype "input"))
      (node (ref "C27") (pin "1") (pinfunction "1_1") (pintype "input"))
      (node (ref "C28") (pin "1") (pinfunction "1_1") (pintype "input"))
      (node (ref "C29") (pin "1") (pinfunction "1_1") (pintype "input"))
      (node (ref "C30") (pin "1") (pinfunction "1_1") (pintype "input"))
      (node (ref "C31") (pin "1") (pinfunction "1_1") (pintype "input"))
      (node (ref "C32") (pin "1") (pinfunction "1_1") (pintype "input"))
      (node (ref "C33") (pin "1") (pinfunction "1_1") (pintype "input"))
      (node (ref "C34") (pin "1") (pinfunction "1_1") (pintype "input"))
      (node (ref "C35") (pin "1") (pinfunction "1_1") (pintype "input"))
      (node (ref "C36") (pin "1") (pinfunction "1_1") (pintype "input"))
      (node (ref "C37") (pin "1") (pinfunction "1_1") (pintype "input"))
      (node (ref "C38") (pin "1") (pinfunction "1_1") (pintype "input"))
      (node (ref "C39") (pin "1") (pinfunction "1_1") (pintype "input"))
      (node (ref "C40") (pin "1") (pinfunction "1_1") (pintype "input"))
      (node (ref "C41") (pin "1") (pinfunction "1_1") (pintype "input"))
      (node (ref "C42") (pin "1") (pinfunction "1_1") (pintype "input"))
      (node (ref "C43") (pin "1") (pinfunction "1_1") (pintype "input"))
      (node (ref "C44") (pin "1") (pinfunction "1_1") (pintype "input"))
      (node (ref "C45") (pin "1") (pinfunction "1_1") (pintype "input"))
      (node (ref "C46") (pin "1") (pinfunction "1_1") (pintype "input"))
      (node (ref "C47") (pin "1") (pinfunction "1_1") (pintype "input"))
      (node (ref "C48") (pin "1") (pinfunction "1_1") (pintype "input"))
      (node (ref "C49") (pin "1") (pinfunction "1_1") (pintype "input"))
      (node (ref "C50") (pin "1") (pinfunction "1_1") (pintype "input"))
      (node (ref "C51") (pin "1") (pinfunction "1_1") (pintype "input"))
      (node (ref "C52") (pin "1") (pinfunction "1_1") (pintype "input"))
      (node (ref "C53") (pin "1") (pinfunction "1_1") (pintype "input"))
      (node (ref "C54") (pin "1") (pinfunction "1_1") (pintype "input"))
      (node (ref "C6") (pin "2") (pinfunction "2_2") (pintype "input"))
      (node (ref "C7") (pin "2") (pinfunction "2_2") (pintype "input"))
      (node (ref "R15") (pin "2") (pinfunction "2_2") (pintype "input"))
      (node (ref "R5") (pin "1") (pinfunction "1_1") (pintype "input"))
      (node (ref "R6") (pin "1") (pinfunction "1_1") (pintype "input"))
      (node (ref "U19") (pin "1") (pinfunction "1_1") (pintype "unspecified"))
      (node (ref "U2") (pin "12") (pinfunction "SNA_12") (pintype "input"))
      (node (ref "U2") (pin "13") (pinfunction "SNB_13") (pintype "input"))
      (node (ref "U2") (pin "14") (pinfunction "SPB_14") (pintype "input"))
      (node (ref "U2") (pin "2") (pinfunction "PGND_2") (pintype "input"))
      (node (ref "U2") (pin "22") (pinfunction "SNC_22") (pintype "input"))
      (node (ref "U7") (pin "1") (pinfunction "S_1") (pintype "input"))
      (node (ref "U7") (pin "2") (pinfunction "S_2") (pintype "input"))
      (node (ref "U7") (pin "3") (pinfunction "S_3") (pintype "input"))
    )
    (net (code "5") (name "CAL") (class "Default")
      (node (ref "U2") (pin "34") (pinfunction "CAL_34") (pintype "input"))
    )
    (net (code "6") (name "CANH") (class "Default")
      (node (ref "CN1") (pin "1") (pinfunction "1_1") (pintype "input"))
      (node (ref "CN1") (pin "4") (pinfunction "4_4") (pintype "input"))
      (node (ref "R16") (pin "2") (pinfunction "2_2") (pintype "input"))
      (node (ref "U3") (pin "7") (pinfunction "CANH_7") (pintype "unspecified"))
    )
    (net (code "7") (name "CANL") (class "Default")
      (node (ref "CN1") (pin "2") (pinfunction "2_2") (pintype "input"))
      (node (ref "CN1") (pin "3") (pinfunction "3_3") (pintype "input"))
      (node (ref "R16") (pin "1") (pinfunction "1_1") (pintype "input"))
      (node (ref "U3") (pin "6") (pinfunction "CANL_6") (pintype "unspecified"))
    )
    (net (code "8") (name "CLK_MAG") (class "Default")
      (node (ref "U1") (pin "10") (pinfunction "PA5_10") (pintype "unspecified"))
      (node (ref "U18") (pin "2") (pinfunction "CLK_2") (pintype "unspecified"))
    )
    (net (code "9") (name "CS_MAG") (class "Default")
      (node (ref "R1") (pin "2") (pinfunction "2_2") (pintype "input"))
      (node (ref "R19") (pin "1") (pinfunction "1_1") (pintype "input"))
      (node (ref "U1") (pin "9") (pinfunction "PA4_9") (pintype "unspecified"))
      (node (ref "U18") (pin "1") (pinfunction "CSn_1") (pintype "unspecified"))
    )
    (net (code "10") (name "DVDD") (class "Default")
      (node (ref "C10") (pin "2") (pinfunction "2_2") (pintype "unspecified"))
      (node (ref "U2") (pin "36") (pinfunction "DVDD_36") (pintype "input"))
    )
    (net (code "11") (name "ENABLE") (class "Default")
      (node (ref "U1") (pin "13") (pinfunction "PB0_13") (pintype "unspecified"))
      (node (ref "U2") (pin "38") (pinfunction "INLA_38") (pintype "input"))
      (node (ref "U2") (pin "40") (pinfunction "INLB_40") (pintype "input"))
      (node (ref "U2") (pin "42") (pinfunction "INLC_42") (pintype "input"))
    )
    (net (code "12") (name "ENC_A") (class "Default")
      (node (ref "H2") (pin "3") (pinfunction "3_3") (pintype "unspecified"))
      (node (ref "R17") (pin "2") (pinfunction "2_2") (pintype "input"))
      (node (ref "U1") (pin "30") (pinfunction "PB7_30") (pintype "unspecified"))
    )
    (net (code "13") (name "ENC_B") (class "Default")
      (node (ref "H2") (pin "2") (pinfunction "2_2") (pintype "unspecified"))
      (node (ref "R18") (pin "2") (pinfunction "2_2") (pintype "input"))
      (node (ref "U1") (pin "29") (pinfunction "PB6_29") (pintype "unspecified"))
    )
    (net (code "14") (name "FB") (class "Default")
      (node (ref "R13") (pin "2") (pinfunction "2_2") (pintype "input"))
      (node (ref "R14") (pin "1") (pinfunction "1_1") (pintype "input"))
      (node (ref "U2") (pin "1") (pinfunction "FB_1") (pintype "input"))
    )
    (net (code "15") (name "FDCAN_RX") (class "Default")
      (node (ref "U1") (pin "21") (pinfunction "PA11_21") (pintype "unspecified"))
      (node (ref "U3") (pin "4") (pinfunction "RXD_4") (pintype "unspecified"))
    )
    (net (code "16") (name "FDCAN_TX") (class "Default")
      (node (ref "U1") (pin "22") (pinfunction "PA12_22") (pintype "unspecified"))
      (node (ref "U3") (pin "1") (pinfunction "TXD_1") (pintype "unspecified"))
    )
    (net (code "17") (name "GHA") (class "Default")
      (node (ref "U2") (pin "8") (pinfunction "GHA_8") (pintype "input"))
      (node (ref "U4") (pin "4") (pinfunction "G_4") (pintype "input"))
    )
    (net (code "18") (name "GHB") (class "Default")
      (node (ref "U2") (pin "17") (pinfunction "GHB_17") (pintype "input"))
      (node (ref "U6") (pin "4") (pinfunction "G_4") (pintype "input"))
    )
    (net (code "19") (name "GHC") (class "Default")
      (node (ref "U2") (pin "18") (pinfunction "GHC_18") (pintype "input"))
      (node (ref "U8") (pin "4") (pinfunction "G_4") (pintype "input"))
    )
    (net (code "20") (name "GLA") (class "Default")
      (node (ref "U2") (pin "10") (pinfunction "GLA_10") (pintype "input"))
      (node (ref "U5") (pin "4") (pinfunction "G_4") (pintype "input"))
    )
    (net (code "21") (name "GLB") (class "Default")
      (node (ref "U2") (pin "15") (pinfunction "GLB_15") (pintype "input"))
      (node (ref "U7") (pin "4") (pinfunction "G_4") (pintype "input"))
    )
    (net (code "22") (name "GLC") (class "Default")
      (node (ref "U2") (pin "20") (pinfunction "GLC_20") (pintype "input"))
      (node (ref "U9") (pin "4") (pinfunction "G_4") (pintype "input"))
    )
    (net (code "23") (name "GND") (class "Default")
      (node (ref "C1") (pin "1") (pinfunction "1_1") (pintype "input"))
      (node (ref "C10") (pin "1") (pinfunction "1_1") (pintype "unspecified"))
      (node (ref "C12") (pin "2") (pinfunction "2_2") (pintype "unspecified"))
      (node (ref "C13") (pin "2") (pinfunction "2_2") (pintype "unspecified"))
      (node (ref "C14") (pin "2") (pinfunction "2_2") (pintype "unspecified"))
      (node (ref "C2") (pin "1") (pinfunction "1_1") (pintype "input"))
      (node (ref "C55") (pin "1") (pinfunction "1_1") (pintype "unspecified"))
      (node (ref "C56") (pin "1") (pinfunction "1_1") (pintype "input"))
      (node (ref "C57") (pin "2") (pinfunction "2_2") (pintype "input"))
      (node (ref "C58") (pin "1") (pinfunction "1_1") (pintype "input"))
      (node (ref "C59") (pin "1") (pinfunction "1_1") (pintype "unspecified"))
      (node (ref "C9") (pin "1") (pinfunction "1_1") (pintype "input"))
      (node (ref "D1") (pin "2") (pinfunction "A_2") (pintype "input"))
      (node (ref "H2") (pin "1") (pinfunction "1_1") (pintype "unspecified"))
      (node (ref "LED1") (pin "1") (pinfunction "-_1") (pintype "input"))
      (node (ref "R10") (pin "2") (pinfunction "2_2") (pintype "input"))
      (node (ref "R11") (pin "2") (pinfunction "2_2") (pintype "input"))
      (node (ref "R12") (pin "2") (pinfunction "2_2") (pintype "input"))
      (node (ref "R14") (pin "2") (pinfunction "2_2") (pintype "input"))
      (node (ref "R15") (pin "1") (pinfunction "1_1") (pintype "input"))
      (node (ref "R9") (pin "2") (pinfunction "2_2") (pintype "input"))
      (node (ref "U1") (pin "14") (pinfunction "VSSA_14") (pintype "unspecified"))
      (node (ref "U1") (pin "16") (pinfunction "VSS_16") (pintype "unspecified"))
      (node (ref "U1") (pin "31") (pinfunction "PB8-BOOT0_31") (pintype "unspecified"))
      (node (ref "U1") (pin "32") (pinfunction "VSS_32") (pintype "unspecified"))
      (node (ref "U10") (pin "2") (pinfunction "2_2") (pintype "unspecified"))
      (node (ref "U11") (pin "2") (pinfunction "2_2") (pintype "unspecified"))
      (node (ref "U12") (pin "2") (pinfunction "2_2") (pintype "unspecified"))
      (node (ref "U18") (pin "13") (pinfunction "GND_13") (pintype "unspecified"))
      (node (ref "U2") (pin "27") (pinfunction "DGND_27") (pintype "input"))
      (node (ref "U2") (pin "35") (pinfunction "AGND_35") (pintype "input"))
      (node (ref "U2") (pin "43") (pinfunction "BGND_43") (pintype "input"))
      (node (ref "U20") (pin "2") (pinfunction "2_2") (pintype "input"))
      (node (ref "U3") (pin "2") (pinfunction "GND_2") (pintype "unspecified"))
    )
    (net (code "24") (name "LP_SOA") (class "Default")
      (node (ref "C57") (pin "1") (pinfunction "1_1") (pintype "input"))
      (node (ref "U1") (pin "5") (pinfunction "PA0_5") (pintype "unspecified"))
      (node (ref "U14") (pin "2") (pinfunction "2_2") (pintype "unspecified"))
    )
    (net (code "25") (name "LP_SOC") (class "Default")
      (node (ref "C58") (pin "2") (pinfunction "2_2") (pintype "input"))
      (node (ref "U1") (pin "6") (pinfunction "PA1_6") (pintype "unspecified"))
      (node (ref "U15") (pin "2") (pinfunction "2_2") (pintype "unspecified"))
    )
    (net (code "26") (name "MISO_MAG") (class "Default")
      (node (ref "U1") (pin "11") (pinfunction "PA6_11") (pintype "unspecified"))
      (node (ref "U18") (pin "3") (pinfunction "MISO_3") (pintype "unspecified"))
    )
    (net (code "27") (name "MOSI_MAG") (class "Default")
      (node (ref "U1") (pin "12") (pinfunction "PA7_12") (pintype "unspecified"))
      (node (ref "U18") (pin "4") (pinfunction "MOSI_4") (pintype "unspecified"))
    )
    (net (code "28") (name "NFAULT") (class "Default")
      (node (ref "R7") (pin "1") (pinfunction "1_1") (pintype "input"))
      (node (ref "R8") (pin "1") (pinfunction "1_1") (pintype "input"))
      (node (ref "U2") (pin "28") (pinfunction "nFAULT_28") (pintype "input"))
    )
    (net (code "29") (name "Net-(D1-C)") (class "Default")
      (node (ref "C11") (pin "1") (pinfunction "1_1") (pintype "input"))
      (node (ref "D1") (pin "1") (pinfunction "C_1") (pintype "input"))
      (node (ref "L2") (pin "1") (pinfunction "1_1") (pintype "input"))
      (node (ref "U2") (pin "45") (pinfunction "SW_45") (pintype "input"))
    )
    (net (code "30") (name "Net-(LED1-+)") (class "Default")
      (node (ref "LED1") (pin "2") (pinfunction "+_2") (pintype "input"))
      (node (ref "R4") (pin "1") (pinfunction "1_1") (pintype "input"))
    )
    (net (code "31") (name "Net-(LED2--)") (class "Default")
      (node (ref "LED2") (pin "1") (pinfunction "-_1") (pintype "input"))
      (node (ref "R8") (pin "2") (pinfunction "2_2") (pintype "input"))
    )
    (net (code "32") (name "Net-(U2-CB)") (class "Default")
      (node (ref "C11") (pin "2") (pinfunction "2_2") (pintype "input"))
      (node (ref "U2") (pin "44") (pinfunction "CB_44") (pintype "input"))
    )
    (net (code "33") (name "Net-(U2-CPH)") (class "Default")
      (node (ref "C5") (pin "1") (pinfunction "1_1") (pintype "input"))
      (node (ref "U2") (pin "4") (pinfunction "CPH_4") (pintype "input"))
    )
    (net (code "34") (name "Net-(U2-CPL)") (class "Default")
      (node (ref "C5") (pin "2") (pinfunction "2_2") (pintype "input"))
      (node (ref "U2") (pin "3") (pinfunction "CPL_3") (pintype "input"))
    )
    (net (code "35") (name "Net-(U2-GAIN)") (class "Default")
      (node (ref "R10") (pin "1") (pinfunction "1_1") (pintype "input"))
      (node (ref "U2") (pin "32") (pinfunction "GAIN_32") (pintype "input"))
    )
    (net (code "36") (name "Net-(U2-IDRIVE)") (class "Default")
      (node (ref "R12") (pin "1") (pinfunction "1_1") (pintype "input"))
      (node (ref "U2") (pin "30") (pinfunction "IDRIVE_30") (pintype "input"))
    )
    (net (code "37") (name "Net-(U2-MODE)") (class "Default")
      (node (ref "R9") (pin "1") (pinfunction "1_1") (pintype "input"))
      (node (ref "U2") (pin "29") (pinfunction "MODE_29") (pintype "input"))
    )
    (net (code "38") (name "Net-(U2-VCP)") (class "Default")
      (node (ref "C8") (pin "2") (pinfunction "2_2") (pintype "unspecified"))
      (node (ref "U2") (pin "5") (pinfunction "VCP_5") (pintype "input"))
    )
    (net (code "39") (name "Net-(U2-VDS)") (class "Default")
      (node (ref "R11") (pin "1") (pinfunction "1_1") (pintype "input"))
      (node (ref "U2") (pin "31") (pinfunction "VDS_31") (pintype "input"))
    )
    (net (code "40") (name "PHASEA") (class "Default")
      (node (ref "U2") (pin "9") (pinfunction "SHA_9") (pintype "input"))
      (node (ref "U4") (pin "1") (pinfunction "S_1") (pintype "input"))
      (node (ref "U4") (pin "2") (pinfunction "S_2") (pintype "input"))
      (node (ref "U4") (pin "3") (pinfunction "S_3") (pintype "input"))
      (node (ref "U5") (pin "5") (pinfunction "D_5") (pintype "input"))
      (node (ref "U5") (pin "6") (pinfunction "D_6") (pintype "input"))
      (node (ref "U5") (pin "7") (pinfunction "D_7") (pintype "input"))
      (node (ref "U5") (pin "8") (pinfunction "D_8") (pintype "input"))
    )
    (net (code "41") (name "PHASEB") (class "Default")
      (node (ref "U2") (pin "16") (pinfunction "SHB_16") (pintype "input"))
      (node (ref "U6") (pin "1") (pinfunction "S_1") (pintype "input"))
      (node (ref "U6") (pin "2") (pinfunction "S_2") (pintype "input"))
      (node (ref "U6") (pin "3") (pinfunction "S_3") (pintype "input"))
      (node (ref "U7") (pin "5") (pinfunction "D_5") (pintype "input"))
      (node (ref "U7") (pin "6") (pinfunction "D_6") (pintype "input"))
      (node (ref "U7") (pin "7") (pinfunction "D_7") (pintype "input"))
      (node (ref "U7") (pin "8") (pinfunction "D_8") (pintype "input"))
    )
    (net (code "42") (name "PHASEC") (class "Default")
      (node (ref "U2") (pin "19") (pinfunction "SHC_19") (pintype "input"))
      (node (ref "U8") (pin "1") (pinfunction "S_1") (pintype "input"))
      (node (ref "U8") (pin "2") (pinfunction "S_2") (pintype "input"))
      (node (ref "U8") (pin "3") (pinfunction "S_3") (pintype "input"))
      (node (ref "U9") (pin "5") (pinfunction "D_5") (pintype "input"))
      (node (ref "U9") (pin "6") (pinfunction "D_6") (pintype "input"))
      (node (ref "U9") (pin "7") (pinfunction "D_7") (pintype "input"))
      (node (ref "U9") (pin "8") (pinfunction "D_8") (pintype "input"))
    )
    (net (code "43") (name "PWMA") (class "Default")
      (node (ref "U1") (pin "20") (pinfunction "PA10_20") (pintype "unspecified"))
      (node (ref "U2") (pin "37") (pinfunction "INHA_37") (pintype "input"))
    )
    (net (code "44") (name "PWMB") (class "Default")
      (node (ref "U1") (pin "19") (pinfunction "PA9_19") (pintype "unspecified"))
      (node (ref "U2") (pin "39") (pinfunction "INHB_39") (pintype "input"))
    )
    (net (code "45") (name "PWMC") (class "Default")
      (node (ref "U1") (pin "18") (pinfunction "PA8_18") (pintype "unspecified"))
      (node (ref "U2") (pin "41") (pinfunction "INHC_41") (pintype "input"))
    )
    (net (code "46") (name "SOA") (class "Default")
      (node (ref "U14") (pin "1") (pinfunction "1_1") (pintype "unspecified"))
      (node (ref "U2") (pin "25") (pinfunction "SOA_25") (pintype "input"))
    )
    (net (code "47") (name "SOB") (class "Default")
      (node (ref "U2") (pin "24") (pinfunction "SOB_24") (pintype "input"))
    )
    (net (code "48") (name "SOC") (class "Default")
      (node (ref "U15") (pin "1") (pinfunction "1_1") (pintype "unspecified"))
      (node (ref "U2") (pin "23") (pinfunction "SOC_23") (pintype "input"))
    )
    (net (code "49") (name "SPA") (class "Default")
      (node (ref "R5") (pin "2") (pinfunction "2_2") (pintype "input"))
      (node (ref "U2") (pin "11") (pinfunction "SPA_11") (pintype "input"))
      (node (ref "U5") (pin "1") (pinfunction "S_1") (pintype "input"))
      (node (ref "U5") (pin "2") (pinfunction "S_2") (pintype "input"))
      (node (ref "U5") (pin "3") (pinfunction "S_3") (pintype "input"))
    )
    (net (code "50") (name "SPC") (class "Default")
      (node (ref "R6") (pin "2") (pinfunction "2_2") (pintype "input"))
      (node (ref "U2") (pin "21") (pinfunction "SPC_21") (pintype "input"))
      (node (ref "U9") (pin "1") (pinfunction "S_1") (pintype "input"))
      (node (ref "U9") (pin "2") (pinfunction "S_2") (pintype "input"))
      (node (ref "U9") (pin "3") (pinfunction "S_3") (pintype "input"))
    )
    (net (code "51") (name "SWCLK") (class "Default")
      (node (ref "U1") (pin "24") (pinfunction "PA14_24") (pintype "unspecified"))
      (node (ref "U20") (pin "4") (pinfunction "4_4") (pintype "input"))
    )
    (net (code "52") (name "SWIO") (class "Default")
      (node (ref "U1") (pin "23") (pinfunction "PA13_23") (pintype "unspecified"))
      (node (ref "U20") (pin "3") (pinfunction "3_3") (pintype "input"))
    )
    (net (code "53") (name "SWO") (class "Default")
      (node (ref "U1") (pin "26") (pinfunction "PB3_26") (pintype "unspecified"))
    )
    (net (code "54") (name "unconnected-(CN1-Pad5)") (class "Default")
      (node (ref "CN1") (pin "5") (pinfunction "5_5") (pintype "input"))
    )
    (net (code "55") (name "unconnected-(CN1-Pad6)") (class "Default")
      (node (ref "CN1") (pin "6") (pinfunction "6_6") (pintype "input"))
    )
    (net (code "56") (name "unconnected-(U1-PA2-Pad7)") (class "Default")
      (node (ref "U1") (pin "7") (pinfunction "PA2_7") (pintype "unspecified"))
    )
    (net (code "57") (name "unconnected-(U1-PA3-Pad8)") (class "Default")
      (node (ref "U1") (pin "8") (pinfunction "PA3_8") (pintype "unspecified"))
    )
    (net (code "58") (name "unconnected-(U1-PA15-Pad25)") (class "Default")
      (node (ref "U1") (pin "25") (pinfunction "PA15_25") (pintype "unspecified"))
    )
    (net (code "59") (name "unconnected-(U1-PB4-Pad27)") (class "Default")
      (node (ref "U1") (pin "27") (pinfunction "PB4_27") (pintype "unspecified"))
    )
    (net (code "60") (name "unconnected-(U1-PB5-Pad28)") (class "Default")
      (node (ref "U1") (pin "28") (pinfunction "PB5_28") (pintype "unspecified"))
    )
    (net (code "61") (name "unconnected-(U1-PF0-OSC_IN-Pad2)") (class "Default")
      (node (ref "U1") (pin "2") (pinfunction "PF0-OSC_IN_2") (pintype "unspecified"))
    )
    (net (code "62") (name "unconnected-(U1-PF1-OSC_OUT-Pad3)") (class "Default")
      (node (ref "U1") (pin "3") (pinfunction "PF1-OSC_OUT_3") (pintype "unspecified"))
    )
    (net (code "63") (name "unconnected-(U1-PG10-NRST-Pad4)") (class "Default")
      (node (ref "U1") (pin "4") (pinfunction "PG10-NRST_4") (pintype "unspecified"))
    )
    (net (code "64") (name "unconnected-(U2-EP-Pad49)") (class "Default")
      (node (ref "U2") (pin "49") (pinfunction "EP_49") (pintype "input"))
    )
    (net (code "65") (name "unconnected-(U2-NC-Pad46)") (class "Default")
      (node (ref "U2") (pin "46") (pinfunction "NC_46") (pintype "input"))
    )
    (net (code "66") (name "unconnected-(U2-nSHDN-Pad48)") (class "Default")
      (node (ref "U2") (pin "48") (pinfunction "nSHDN_48") (pintype "input"))
    )
    (net (code "67") (name "unconnected-(U3-NC-Pad5)") (class "Default")
      (node (ref "U3") (pin "5") (pinfunction "NC_5") (pintype "unspecified"))
    )
    (net (code "68") (name "unconnected-(U3-NC-Pad8)") (class "Default")
      (node (ref "U3") (pin "8") (pinfunction "NC_8") (pintype "unspecified"))
    )
    (net (code "69") (name "unconnected-(U18-PWM-Pad14)") (class "Default")
      (node (ref "U18") (pin "14") (pinfunction "PWM_14") (pintype "unspecified"))
    )
    (net (code "70") (name "unconnected-(U18-TEST-Pad5)") (class "Default")
      (node (ref "U18") (pin "5") (pinfunction "TEST_5") (pintype "unspecified"))
    )
    (net (code "71") (name "unconnected-(U18-TEST-Pad6)") (class "Default")
      (node (ref "U18") (pin "6") (pinfunction "TEST_6") (pintype "unspecified"))
    )
    (net (code "72") (name "unconnected-(U18-TEST-Pad7)") (class "Default")
      (node (ref "U18") (pin "7") (pinfunction "TEST_7") (pintype "unspecified"))
    )
    (net (code "73") (name "unconnected-(U18-TEST-Pad8)") (class "Default")
      (node (ref "U18") (pin "8") (pinfunction "TEST_8") (pintype "unspecified"))
    )
    (net (code "74") (name "unconnected-(U18-TEST-Pad9)") (class "Default")
      (node (ref "U18") (pin "9") (pinfunction "TEST_9") (pintype "unspecified"))
    )
    (net (code "75") (name "unconnected-(U18-TEST-Pad10)") (class "Default")
      (node (ref "U18") (pin "10") (pinfunction "TEST_10") (pintype "unspecified"))
    )
    (net (code "76") (name "unconnected-(U18-VDD5V-Pad11)") (class "Default")
      (node (ref "U18") (pin "11") (pinfunction "VDD5V_11") (pintype "unspecified"))
    )
    (net (code "77") (name "unconnected-(U19-Pad3)") (class "Default")
      (node (ref "U19") (pin "3") (pinfunction "3_3") (pintype "unspecified"))
    )
    (net (code "78") (name "unconnected-(U19-Pad4)") (class "Default")
      (node (ref "U19") (pin "4") (pinfunction "4_4") (pintype "unspecified"))
    )
  )
)
